# Button.net
KiCad netlist of a schematic drawn in Altium Designer
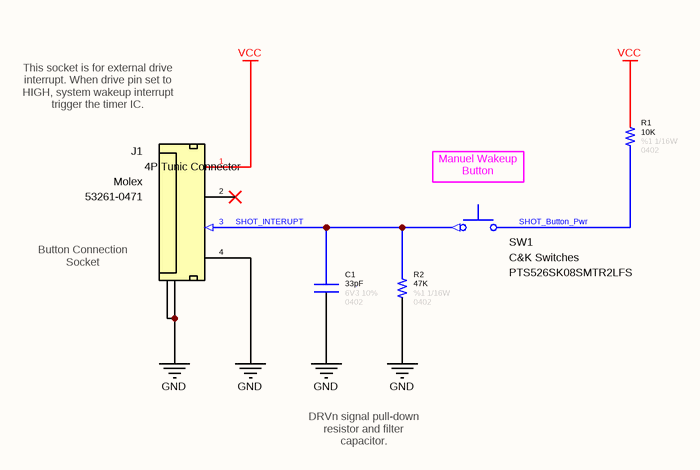
[diagram p0: Button.SchDoc]

(export (version "E")
  (design (tool "Eeschema 10.0.6"))
  (components
    (comp (ref "C1")
      (value "33pF")
      (footprint "CAPACITOR_0402")
      (description "Capacitor - 33pF [0402] (Ceramic)")
      (fields
        (field (name "MANUFACTURER PART NUMBER") "C0402C330J9RACAUTO")
        (field (name "TOLERANCE") "10%")
        (field (name "CASE") "0402")
        (field (name "VOLTAGE") "6V3")
      )
      (libsource (lib "P101DA_Library") (part "Capacitor - 33pF [0402-6V3]"))
    )
    (comp (ref "J1")
      (value "4P SMD Tunic Connector")
      (footprint "Connector_Tunic 4P")
      (description "Mini Tunic Connector with 4P")
      (fields
        (field (name "MANUFACTURER NAME") "Molex")
        (field (name "MANUFACTURER PART NUMBER") "53261-0471")
      )
      (libsource (lib "P101DA_Library") (part "Connector - Mini Tunic 4P (1.25)"))
    )
    (comp (ref "R1")
      (value "10K")
      (footprint "RESISTOR_0402")
      (description "Thick Film Resistors - SMD 1/16 W 10 KOhm 1%")
      (fields
        (field (name "MANUFACTURER PART NUMBER") "CRCW040210K0FKED")
        (field (name "TOLERANCE") "%1")
        (field (name "CASE") "0402")
        (field (name "POWER") "1/16W")
        (field (name "Comment") "10K - 0402 - %1 - 1/16W")
      )
      (libsource (lib "P101DA_Library") (part "Resistor - 10K [0402]"))
    )
    (comp (ref "R2")
      (value "47K")
      (footprint "RESISTOR_0402")
      (description "Thick Film Resistors - SMD 1/16 W 47 KOhm 1%")
      (fields
        (field (name "MANUFACTURER PART NUMBER") "CRCW040247K0FKED")
        (field (name "TOLERANCE") "%1")
        (field (name "CASE") "0402")
        (field (name "POWER") "1/16W")
        (field (name "Comment") "47K - 0402 - %1 - 1/16W")
      )
      (libsource (lib "P101DA_Library") (part "Resistor - 47K [0402]"))
    )
    (comp (ref "SW1")
      (value "PTS526SK08SMTR2LFS")
      (footprint "PTS526_Switch")
      (description "Switch Tactile N.O. SPST Flush Round Button Gull Wing 0.05A 12VDC 200000Cycles 2.45N SMD T/R")
      (fields
        (field (name "MANUFACTURER NAME") "C&K Switches")
        (field (name "MANUFACTURER PART NUMBER") "PTS526SK08SMTR2LFS")
      )
      (libsource (lib "P101DA_Library") (part "Switch - Push Button"))
    )
  )
  (nets
    (net (code "1") (name "/SHOT_Button_Pwr") (class "Default")
      (node (ref "R1") (pin "1") (pinfunction "1_1") (pintype "passive"))
      (node (ref "SW1") (pin "2") (pinfunction "COM_2") (pintype "passive"))
    )
    (net (code "2") (name "/SHOT_INTERUPT") (class "Default")
      (node (ref "C1") (pin "2") (pinfunction "2_2") (pintype "passive"))
      (node (ref "J1") (pin "3") (pinfunction "Pin-3_3") (pintype "input"))
      (node (ref "R2") (pin "2") (pinfunction "2_2") (pintype "passive"))
      (node (ref "SW1") (pin "1") (pinfunction "NC_1") (pintype "output"))
    )
    (net (code "3") (name "GND") (class "Default")
      (node (ref "C1") (pin "1") (pinfunction "1_1") (pintype "passive"))
      (node (ref "J1") (pin "4") (pinfunction "Pin-4_4") (pintype "power_in"))
      (node (ref "J1") (pin "5") (pinfunction "GND_5") (pintype "passive"))
      (node (ref "J1") (pin "6") (pinfunction "GND_6") (pintype "passive"))
      (node (ref "R2") (pin "1") (pinfunction "1_1") (pintype "passive"))
    )
    (net (code "4") (name "VCC") (class "Default")
      (node (ref "J1") (pin "1") (pinfunction "Pin-1_1") (pintype "power_in"))
      (node (ref "R1") (pin "2") (pinfunction "2_2") (pintype "passive"))
    )
    (net (code "5") (name "unconnected-(J1-Pin-2-Pad2)") (class "Default")
      (node (ref "J1") (pin "2") (pinfunction "Pin-2_2") (pintype "passive+no_connect"))
    )
  )
)
